# 13_NB-IOT_Peripheral.net
KiCad netlist of a schematic drawn in Altium Designer
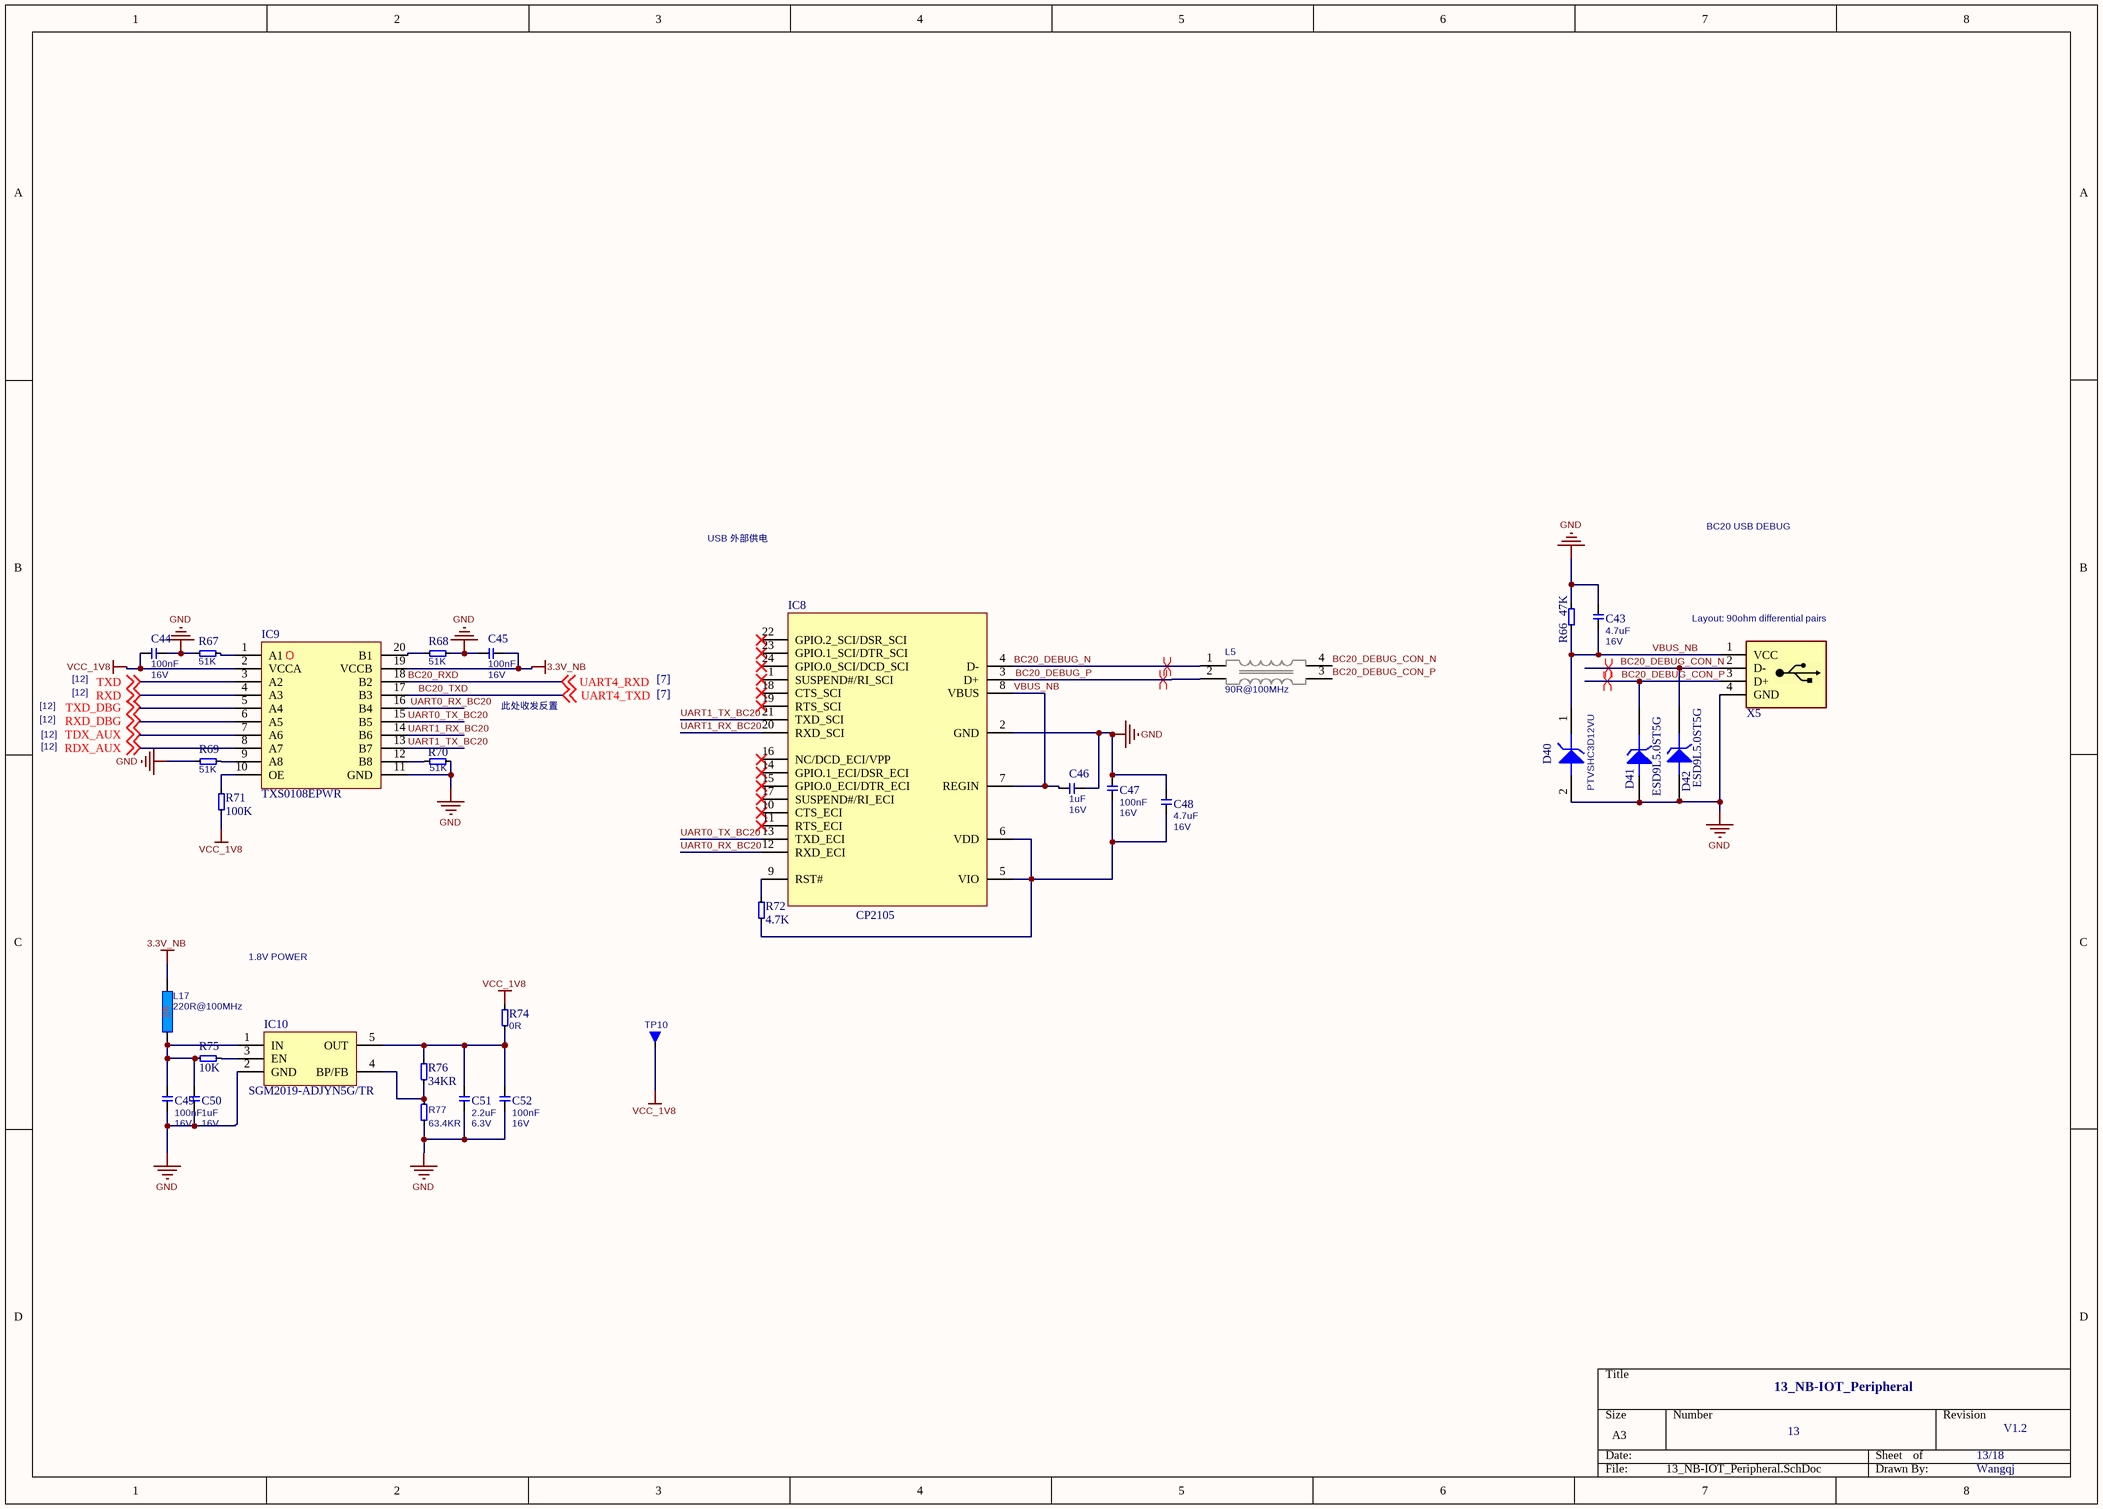
[diagram p0: 13_NB-IOT_Peripheral.SchDoc]

(export (version "E")
  (design (tool "Eeschema 10.0.6"))
  (components
    (comp (ref "C43")
      (value "4.7uF")
      (footprint "T_CAPC0603X33N")
      (description "Capacitor Ceramic X5R 4.7uF 16V 10% 0603")
      (fields (field (name "TOLERANCE") "10%") (field (name "RATING") "16V"))
      (libsource (lib "Apalis Evaluation Board") (part "C-4.7uF-16V-10%-0603-X5R"))
    )
    (comp (ref "C44")
      (value "100nF")
      (footprint "T_CAPC0603X33N")
      (description "Capacitor Ceramic X7R 100nF 16V 10% 0603")
      (fields (field (name "TOLERANCE") "10%") (field (name "RATING") "16V"))
      (libsource (lib "Apalis Evaluation Board") (part "C-X7R-100nF-16V-10%-0603"))
    )
    (comp (ref "C45")
      (value "100nF")
      (footprint "T_CAPC0603X33N")
      (description "Capacitor Ceramic X7R 100nF 16V 10% 0603")
      (fields (field (name "TOLERANCE") "10%") (field (name "RATING") "16V"))
      (libsource (lib "Apalis Evaluation Board") (part "C-X7R-100nF-16V-10%-0603"))
    )
    (comp (ref "C46")
      (value "1uF")
      (footprint "T_CAPC0603X33N")
      (description "Capacitor Ceramic X5R 1uF 16V 10% 0603")
      (fields (field (name "TOLERANCE") "10%") (field (name "RATING") "16V"))
      (libsource (lib "Apalis Evaluation Board") (part "C-1uF-16V-10%-0603-X5R"))
    )
    (comp (ref "C47")
      (value "100nF")
      (footprint "T_CAPC0603X33N")
      (description "Capacitor Ceramic X7R 100nF 16V 10% 0603")
      (fields (field (name "TOLERANCE") "10%") (field (name "RATING") "16V"))
      (libsource (lib "Apalis Evaluation Board") (part "C-100nF-16V-10%-0603-X7R"))
    )
    (comp (ref "C48")
      (value "4.7uF")
      (footprint "T_CAPC0603X33N")
      (description "Capacitor Ceramic X5R 4.7uF 16V 10% 0603")
      (fields (field (name "TOLERANCE") "10%") (field (name "RATING") "16V"))
      (libsource (lib "Apalis Evaluation Board") (part "C-4.7uF-16V-10%-0603-X5R"))
    )
    (comp (ref "C49")
      (value "100nF")
      (footprint "T_CAPC0603X33N")
      (description "Capacitor Ceramic X7R 100nF 16V 10% 0603")
      (fields (field (name "TOLERANCE") "10%") (field (name "RATING") "16V"))
      (libsource (lib "Apalis Evaluation Board") (part "C-X7R-100nF-16V-10%-0603"))
    )
    (comp (ref "C50")
      (value "1uF")
      (footprint "T_CAPC0603X33N")
      (description "Capacitor Ceramic X5R 1uF 16V 10% 0603")
      (fields (field (name "TOLERANCE") "10%") (field (name "RATING") "16V"))
      (libsource (lib "Apalis Evaluation Board") (part "C-X5R-1uF-16V-10%-0603"))
    )
    (comp (ref "C51")
      (value "2.2uF")
      (footprint "T_CAPC0603X33N")
      (description "Capacitor Ceramic X5R 2.2uF 6.3V 20% 0603")
      (fields (field (name "TOLERANCE") "20%") (field (name "RATING") "6.3V"))
      (libsource (lib "Apalis Evaluation Board") (part "C-X5R-2.2uF-6.3V-20%-0603"))
    )
    (comp (ref "C52")
      (value "100nF")
      (footprint "T_CAPC0603X33N")
      (description "Capacitor Ceramic X7R 100nF 16V 10% 0603")
      (fields (field (name "TOLERANCE") "10%") (field (name "RATING") "16V"))
      (libsource (lib "Apalis Evaluation Board") (part "C-X7R-100nF-16V-10%-0603"))
    )
    (comp (ref "D40")
      (value "PTVSHC3D12VU")
      (footprint "LC-SOD-323")
      (description "TVS Diode")
      (libsource (lib "Apalis Evaluation Board") (part "Diode_TVS"))
    )
    (comp (ref "D41")
      (value "ESD9L5.0ST5G")
      (footprint "LC-SOD-923")
      (description "TVS Diode")
      (libsource (lib "二极管") (part "ZENER3"))
    )
    (comp (ref "D42")
      (value "ESD9L5.0ST5G")
      (footprint "LC-SOD-923")
      (description "TVS Diode")
      (libsource (lib "二极管") (part "ZENER3"))
    )
    (comp (ref "IC8")
      (value "CP2105")
      (footprint "LC-QFN-24_4x4x05P")
      (description "Single-Chip USB To Dual UART Bridge")
      (fields (field (name "MANUCFACTURER PART NO.") "CP2105"))
      (libsource (lib "Apalis Evaluation Board") (part "IC-SILICON-CP2105"))
    )
    (comp (ref "IC9")
      (value "TXS0108EPWR")
      (footprint "LC-TSSOP-20")
      (description "8-Bit Bidirectional Voltage-level Translator")
      (fields (field (name "MANUFACTURER PART NO.") "TXS0108EPWR"))
      (libsource (lib "Apalis Evaluation Board") (part "IC-TI-TXS0108EPWR"))
    )
    (comp (ref "IC10")
      (value "SGM2019-ADJYN5G/TR")
      (footprint "LC-SOT-23-5")
      (description "LDO Input: 2.5V to 5.5V Output:1.2V to 5V")
      (fields (field (name "MANUFACTURER PART NO.") "SGM2019-ADJYN5G/TR"))
      (libsource (lib "Apalis Evaluation Board") (part "IC-SGMICRO-SGM2019"))
    )
    (comp (ref "L5")
      (value "90R@100MHz")
      (footprint "T_Murata_DLW21SN900SQ2")
      (description "Common Mode Choke High Speed 90R 330mA")
      (fields (field (name "TOLERANCE") "25%") (field (name "MANUFACTURER PART NO.") "DLW21SN900SQ2"))
      (libsource (lib "Apalis Evaluation Board") (part "L-Murata-DLW21SN900SQ2-90R@100MHz-330mA-25%"))
    )
    (comp (ref "L17")
      (value "220R@100MHz")
      (footprint "INDC1608X95N")
      (description "220R@100MHz 2A EMI FILTER")
      (fields (field (name "TOLERANCE") "25%"))
      (libsource (lib "Apalis Evaluation Board") (part "L-220R@100MHz-2A-25%-0603"))
    )
    (comp (ref "R66")
      (value "47K")
      (footprint "T_RESC0603X30N")
      (description "Resistor 47 Kohm 63mW 5% 0603")
      (fields (field (name "TOLERANCE") "5%"))
      (libsource (lib "Apalis Evaluation Board") (part "R-47KR-63mW-5%-0603"))
    )
    (comp (ref "R67")
      (value "51K")
      (footprint "T_RESC0603X30N")
      (description "Resistor 51K ohm  5% 0603")
      (fields (field (name "TOLERANCE") "5%"))
      (libsource (lib "Apalis Evaluation Board") (part "R-51K-5%-0603"))
    )
    (comp (ref "R68")
      (value "51K")
      (footprint "T_RESC0603X30N")
      (description "Resistor 51K ohm  5% 0603")
      (fields (field (name "TOLERANCE") "5%"))
      (libsource (lib "Apalis Evaluation Board") (part "R-51K-5%-0603"))
    )
    (comp (ref "R69")
      (value "51K")
      (footprint "T_RESC0603X30N")
      (description "Resistor 51K ohm  5% 0603")
      (fields (field (name "TOLERANCE") "5%"))
      (libsource (lib "Apalis Evaluation Board") (part "R-51K-5%-0603"))
    )
    (comp (ref "R70")
      (value "51K")
      (footprint "T_RESC0603X30N")
      (description "Resistor 51K ohm  5% 0603")
      (fields (field (name "TOLERANCE") "5%"))
      (libsource (lib "Apalis Evaluation Board") (part "R-51K-5%-0603"))
    )
    (comp (ref "R71")
      (value "100K")
      (footprint "T_RESC0603X30N")
      (description "Resistor 100 Kohm 63mW 5% 0603")
      (fields (field (name "TOLERANCE") "5%"))
      (libsource (lib "Apalis Evaluation Board") (part "R-100KR-63mW-5%-0603"))
    )
    (comp (ref "R72")
      (value "4.7K")
      (footprint "t_RESC0603X30N")
      (description "Resistor 4.7 Kohm 63mW 5% 0603")
      (fields (field (name "TOLERANCE") "5%"))
      (libsource (lib "Apalis Evaluation Board") (part "R-4.7kR-63mW-5%-0603"))
    )
    (comp (ref "R74")
      (value "0R")
      (footprint "T_RESC0603X30N")
      (description "Resistor 0 ohm 63mW 1% 0603")
      (fields (field (name "TOLERANCE") "1%"))
      (libsource (lib "Apalis Evaluation Board") (part "R-0R-63mW-1%-0603"))
    )
    (comp (ref "R75")
      (value "10K")
      (footprint "T_RESC0603X30N")
      (description "Resistor 10 Kohm 63mW 5% 0603")
      (fields (field (name "TOLERANCE") "5%"))
      (libsource (lib "Apalis Evaluation Board") (part "R-10KR-63mW-5%-0603"))
    )
    (comp (ref "R76")
      (value "34KR")
      (footprint "T_RESC0603X30N")
      (description "Resistor 34 Kohm 63mW 1% 0603")
      (fields (field (name "TOLERANCE") "1%"))
      (libsource (lib "Apalis Evaluation Board") (part "R-34KR-63mW-1%-0603"))
    )
    (comp (ref "R77")
      (value "63.4KR")
      (footprint "T_RESC0603X30N")
      (description "Resistor 63.4 Kohm  1% 0603")
      (fields (field (name "TOLERANCE") "1%"))
      (libsource (lib "Apalis Evaluation Board") (part "R-63.4KR-1%-0603"))
    )
    (comp (ref "TP10")
      (value "Testpin")
      (footprint "T_TP-THT")
      (description "Testpin TH")
      (libsource (lib "Apalis Evaluation Board") (part "Testpin"))
    )
    (comp (ref "X5")
      (value "CON-USB")
      (footprint "2.54*4p")
      (description "USB  Connector")
      (fields (field (name "MANUFACTURER PART NO.") "73725-0110BLF"))
      (libsource (lib "Apalis Evaluation Board") (part "CON-USB"))
    )
  )
  (nets
    (net (code "1") (name "/BC20_DEBUG_CON_N") (class "Default")
      (node (ref "D42") (pin "2") (pinfunction "K_2") (pintype "passive"))
      (node (ref "L5") (pin "4") (pinfunction "4_4") (pintype "passive"))
      (node (ref "X5") (pin "2") (pinfunction "D-_2") (pintype "passive"))
    )
    (net (code "2") (name "/BC20_DEBUG_CON_P") (class "Default")
      (node (ref "D41") (pin "2") (pinfunction "K_2") (pintype "passive"))
      (node (ref "L5") (pin "3") (pinfunction "3_3") (pintype "passive"))
      (node (ref "X5") (pin "3") (pinfunction "D+_3") (pintype "passive"))
    )
    (net (code "3") (name "/BC20_DEBUG_N") (class "Default")
      (node (ref "IC8") (pin "4") (pinfunction "D-_4") (pintype "passive"))
      (node (ref "L5") (pin "1") (pinfunction "1_1") (pintype "passive"))
    )
    (net (code "4") (name "/BC20_DEBUG_P") (class "Default")
      (node (ref "IC8") (pin "3") (pinfunction "D+_3") (pintype "passive"))
      (node (ref "L5") (pin "2") (pinfunction "2_2") (pintype "passive"))
    )
    (net (code "5") (name "/UART0_RX_BC20") (class "Default")
      (node (ref "IC8") (pin "12") (pinfunction "RXD_ECI_12") (pintype "passive"))
      (node (ref "IC9") (pin "16") (pinfunction "B4_16") (pintype "passive"))
    )
    (net (code "6") (name "/UART0_TX_BC20") (class "Default")
      (node (ref "IC8") (pin "13") (pinfunction "TXD_ECI_13") (pintype "passive"))
      (node (ref "IC9") (pin "15") (pinfunction "B5_15") (pintype "passive"))
    )
    (net (code "7") (name "/UART1_RX_BC20") (class "Default")
      (node (ref "IC8") (pin "20") (pinfunction "RXD_SCI_20") (pintype "passive"))
      (node (ref "IC9") (pin "14") (pinfunction "B6_14") (pintype "passive"))
    )
    (net (code "8") (name "/UART1_TX_BC20") (class "Default")
      (node (ref "IC8") (pin "21") (pinfunction "TXD_SCI_21") (pintype "passive"))
      (node (ref "IC9") (pin "13") (pinfunction "B7_13") (pintype "passive"))
    )
    (net (code "9") (name "/VBUS_NB") (class "Default")
      (node (ref "C43") (pin "1") (pinfunction "1_1") (pintype "passive"))
      (node (ref "C46") (pin "1") (pinfunction "1_1") (pintype "passive"))
      (node (ref "D40") (pin "1") (pinfunction "K_1") (pintype "passive"))
      (node (ref "IC8") (pin "7") (pinfunction "REGIN_7") (pintype "passive"))
      (node (ref "IC8") (pin "8") (pinfunction "VBUS_8") (pintype "passive"))
      (node (ref "R66") (pin "1") (pinfunction "1_1") (pintype "passive"))
      (node (ref "X5") (pin "1") (pinfunction "VCC_1") (pintype "power_in"))
    )
    (net (code "10") (name "3.3V_NB") (class "Default")
      (node (ref "C45") (pin "2") (pinfunction "2_2") (pintype "passive"))
      (node (ref "IC9") (pin "19") (pinfunction "VCCB_19") (pintype "passive"))
      (node (ref "L17") (pin "2") (pinfunction "2_2") (pintype "passive"))
    )
    (net (code "11") (name "GND") (class "Default")
      (node (ref "C43") (pin "2") (pinfunction "2_2") (pintype "passive"))
      (node (ref "C44") (pin "2") (pinfunction "2_2") (pintype "passive"))
      (node (ref "C45") (pin "1") (pinfunction "1_1") (pintype "passive"))
      (node (ref "C46") (pin "2") (pinfunction "2_2") (pintype "passive"))
      (node (ref "C47") (pin "2") (pinfunction "2_2") (pintype "passive"))
      (node (ref "C48") (pin "2") (pinfunction "2_2") (pintype "passive"))
      (node (ref "C49") (pin "1") (pinfunction "1_1") (pintype "passive"))
      (node (ref "C50") (pin "1") (pinfunction "1_1") (pintype "passive"))
      (node (ref "C51") (pin "1") (pinfunction "1_1") (pintype "passive"))
      (node (ref "C52") (pin "1") (pinfunction "1_1") (pintype "passive"))
      (node (ref "D40") (pin "2") (pinfunction "A_2") (pintype "passive"))
      (node (ref "D41") (pin "1") (pinfunction "A_1") (pintype "passive"))
      (node (ref "D42") (pin "1") (pinfunction "A_1") (pintype "passive"))
      (node (ref "IC10") (pin "2") (pinfunction "GND_2") (pintype "power_in"))
      (node (ref "IC8") (pin "2") (pinfunction "GND_2") (pintype "power_in"))
      (node (ref "IC9") (pin "11") (pinfunction "GND_11") (pintype "power_in"))
      (node (ref "R66") (pin "2") (pinfunction "2_2") (pintype "passive"))
      (node (ref "R67") (pin "1") (pinfunction "1_1") (pintype "passive"))
      (node (ref "R68") (pin "2") (pinfunction "2_2") (pintype "passive"))
      (node (ref "R69") (pin "1") (pinfunction "1_1") (pintype "passive"))
      (node (ref "R70") (pin "2") (pinfunction "2_2") (pintype "passive"))
      (node (ref "R77") (pin "1") (pinfunction "1_1") (pintype "passive"))
      (node (ref "X5") (pin "4") (pinfunction "GND_4") (pintype "power_in"))
    )
    (net (code "12") (name "Net-(IC8-RST#)") (class "Default")
      (node (ref "IC8") (pin "9") (pinfunction "RST#_9") (pintype "passive"))
      (node (ref "R72") (pin "2") (pinfunction "2_2") (pintype "passive"))
    )
    (net (code "13") (name "Net-(IC8-VDD)") (class "Default")
      (node (ref "C47") (pin "1") (pinfunction "1_1") (pintype "passive"))
      (node (ref "C48") (pin "1") (pinfunction "1_1") (pintype "passive"))
      (node (ref "IC8") (pin "5") (pinfunction "VIO_5") (pintype "power_in"))
      (node (ref "IC8") (pin "6") (pinfunction "VDD_6") (pintype "power_in"))
      (node (ref "R72") (pin "1") (pinfunction "1_1") (pintype "passive"))
    )
    (net (code "14") (name "Net-(IC9-A1)") (class "Default")
      (node (ref "IC9") (pin "1") (pinfunction "A1_1") (pintype "passive"))
      (node (ref "R67") (pin "2") (pinfunction "2_2") (pintype "passive"))
    )
    (net (code "15") (name "Net-(IC9-A8)") (class "Default")
      (node (ref "IC9") (pin "9") (pinfunction "A8_9") (pintype "passive"))
      (node (ref "R69") (pin "2") (pinfunction "2_2") (pintype "passive"))
    )
    (net (code "16") (name "Net-(IC9-B1)") (class "Default")
      (node (ref "IC9") (pin "20") (pinfunction "B1_20") (pintype "passive"))
      (node (ref "R68") (pin "1") (pinfunction "1_1") (pintype "passive"))
    )
    (net (code "17") (name "Net-(IC9-B8)") (class "Default")
      (node (ref "IC9") (pin "12") (pinfunction "B8_12") (pintype "power_in"))
      (node (ref "R70") (pin "1") (pinfunction "1_1") (pintype "passive"))
    )
    (net (code "18") (name "Net-(IC9-OE)") (class "Default")
      (node (ref "IC9") (pin "10") (pinfunction "OE_10") (pintype "passive"))
      (node (ref "R71") (pin "2") (pinfunction "2_2") (pintype "passive"))
    )
    (net (code "19") (name "Net-(IC10-BP{slash}FB)") (class "Default")
      (node (ref "IC10") (pin "4") (pinfunction "BP/FB_4") (pintype "passive"))
      (node (ref "R76") (pin "1") (pinfunction "1_1") (pintype "passive"))
      (node (ref "R77") (pin "2") (pinfunction "2_2") (pintype "passive"))
    )
    (net (code "20") (name "Net-(IC10-EN)") (class "Default")
      (node (ref "IC10") (pin "3") (pinfunction "EN_3") (pintype "passive"))
      (node (ref "R75") (pin "2") (pinfunction "2_2") (pintype "passive"))
    )
    (net (code "21") (name "Net-(IC10-IN)") (class "Default")
      (node (ref "C49") (pin "2") (pinfunction "2_2") (pintype "passive"))
      (node (ref "C50") (pin "2") (pinfunction "2_2") (pintype "passive"))
      (node (ref "IC10") (pin "1") (pinfunction "IN_1") (pintype "power_in"))
      (node (ref "L17") (pin "1") (pinfunction "1_1") (pintype "passive"))
      (node (ref "R75") (pin "1") (pinfunction "1_1") (pintype "passive"))
    )
    (net (code "22") (name "Net-(IC10-OUT)") (class "Default")
      (node (ref "C51") (pin "2") (pinfunction "2_2") (pintype "passive"))
      (node (ref "C52") (pin "2") (pinfunction "2_2") (pintype "passive"))
      (node (ref "IC10") (pin "5") (pinfunction "OUT_5") (pintype "power_in"))
      (node (ref "R74") (pin "1") (pinfunction "1_1") (pintype "passive"))
      (node (ref "R76") (pin "2") (pinfunction "2_2") (pintype "passive"))
    )
    (net (code "23") (name "RDX_AUX") (class "Default")
      (node (ref "IC9") (pin "8") (pinfunction "A7_8") (pintype "passive"))
    )
    (net (code "24") (name "RXD") (class "Default")
      (node (ref "IC9") (pin "4") (pinfunction "A3_4") (pintype "passive"))
    )
    (net (code "25") (name "RXD_DBG") (class "Default")
      (node (ref "IC9") (pin "6") (pinfunction "A5_6") (pintype "passive"))
    )
    (net (code "26") (name "TDX_AUX") (class "Default")
      (node (ref "IC9") (pin "7") (pinfunction "A6_7") (pintype "passive"))
    )
    (net (code "27") (name "TXD") (class "Default")
      (node (ref "IC9") (pin "3") (pinfunction "A2_3") (pintype "passive"))
    )
    (net (code "28") (name "TXD_DBG") (class "Default")
      (node (ref "IC9") (pin "5") (pinfunction "A4_5") (pintype "passive"))
    )
    (net (code "29") (name "UART4_RXD") (class "Default")
      (node (ref "IC9") (pin "18") (pinfunction "B2_18") (pintype "passive"))
    )
    (net (code "30") (name "UART4_TXD") (class "Default")
      (node (ref "IC9") (pin "17") (pinfunction "B3_17") (pintype "passive"))
    )
    (net (code "31") (name "VCC_1V8") (class "Default")
      (node (ref "C44") (pin "1") (pinfunction "1_1") (pintype "passive"))
      (node (ref "IC9") (pin "2") (pinfunction "VCCA_2") (pintype "power_in"))
      (node (ref "R71") (pin "1") (pinfunction "1_1") (pintype "passive"))
      (node (ref "R74") (pin "2") (pinfunction "2_2") (pintype "passive"))
      (node (ref "TP10") (pin "1") (pinfunction "1_1") (pintype "passive"))
    )
    (net (code "32") (name "unconnected-(IC8-CTS_ECI-Pad10)") (class "Default")
      (node (ref "IC8") (pin "10") (pinfunction "CTS_ECI_10") (pintype "passive+no_connect"))
    )
    (net (code "33") (name "unconnected-(IC8-CTS_SCI-Pad18)") (class "Default")
      (node (ref "IC8") (pin "18") (pinfunction "CTS_SCI_18") (pintype "passive+no_connect"))
    )
    (net (code "34") (name "unconnected-(IC8-GPIO.0_ECI{slash}DTR_ECI-Pad15)") (class "Default")
      (node (ref "IC8") (pin "15") (pinfunction "GPIO.0_ECI/DTR_ECI_15") (pintype "passive+no_connect"))
    )
    (net (code "35") (name "unconnected-(IC8-GPIO.0_SCI{slash}DCD_SCI-Pad24)") (class "Default")
      (node (ref "IC8") (pin "24") (pinfunction "GPIO.0_SCI/DCD_SCI_24") (pintype "passive+no_connect"))
    )
    (net (code "36") (name "unconnected-(IC8-GPIO.1_ECI{slash}DSR_ECI-Pad14)") (class "Default")
      (node (ref "IC8") (pin "14") (pinfunction "GPIO.1_ECI/DSR_ECI_14") (pintype "passive+no_connect"))
    )
    (net (code "37") (name "unconnected-(IC8-GPIO.1_SCI{slash}DTR_SCI-Pad23)") (class "Default")
      (node (ref "IC8") (pin "23") (pinfunction "GPIO.1_SCI/DTR_SCI_23") (pintype "passive+no_connect"))
    )
    (net (code "38") (name "unconnected-(IC8-GPIO.2_SCI{slash}DSR_SCI-Pad22)") (class "Default")
      (node (ref "IC8") (pin "22") (pinfunction "GPIO.2_SCI/DSR_SCI_22") (pintype "passive+no_connect"))
    )
    (net (code "39") (name "unconnected-(IC8-NC{slash}DCD_ECI{slash}VPP-Pad16)") (class "Default")
      (node (ref "IC8") (pin "16") (pinfunction "NC/DCD_ECI/VPP_16") (pintype "passive+no_connect"))
    )
    (net (code "40") (name "unconnected-(IC8-RTS_ECI-Pad11)") (class "Default")
      (node (ref "IC8") (pin "11") (pinfunction "RTS_ECI_11") (pintype "passive+no_connect"))
    )
    (net (code "41") (name "unconnected-(IC8-RTS_SCI-Pad19)") (class "Default")
      (node (ref "IC8") (pin "19") (pinfunction "RTS_SCI_19") (pintype "passive+no_connect"))
    )
    (net (code "42") (name "unconnected-(IC8-SUSPEND#{slash}RI_ECI-Pad17)") (class "Default")
      (node (ref "IC8") (pin "17") (pinfunction "SUSPEND#/RI_ECI_17") (pintype "passive+no_connect"))
    )
    (net (code "43") (name "unconnected-(IC8-SUSPEND#{slash}RI_SCI-Pad1)") (class "Default")
      (node (ref "IC8") (pin "1") (pinfunction "SUSPEND#/RI_SCI_1") (pintype "passive+no_connect"))
    )
  )
)
